# project_02.net
KiCad netlist of a schematic drawn in EAGLE
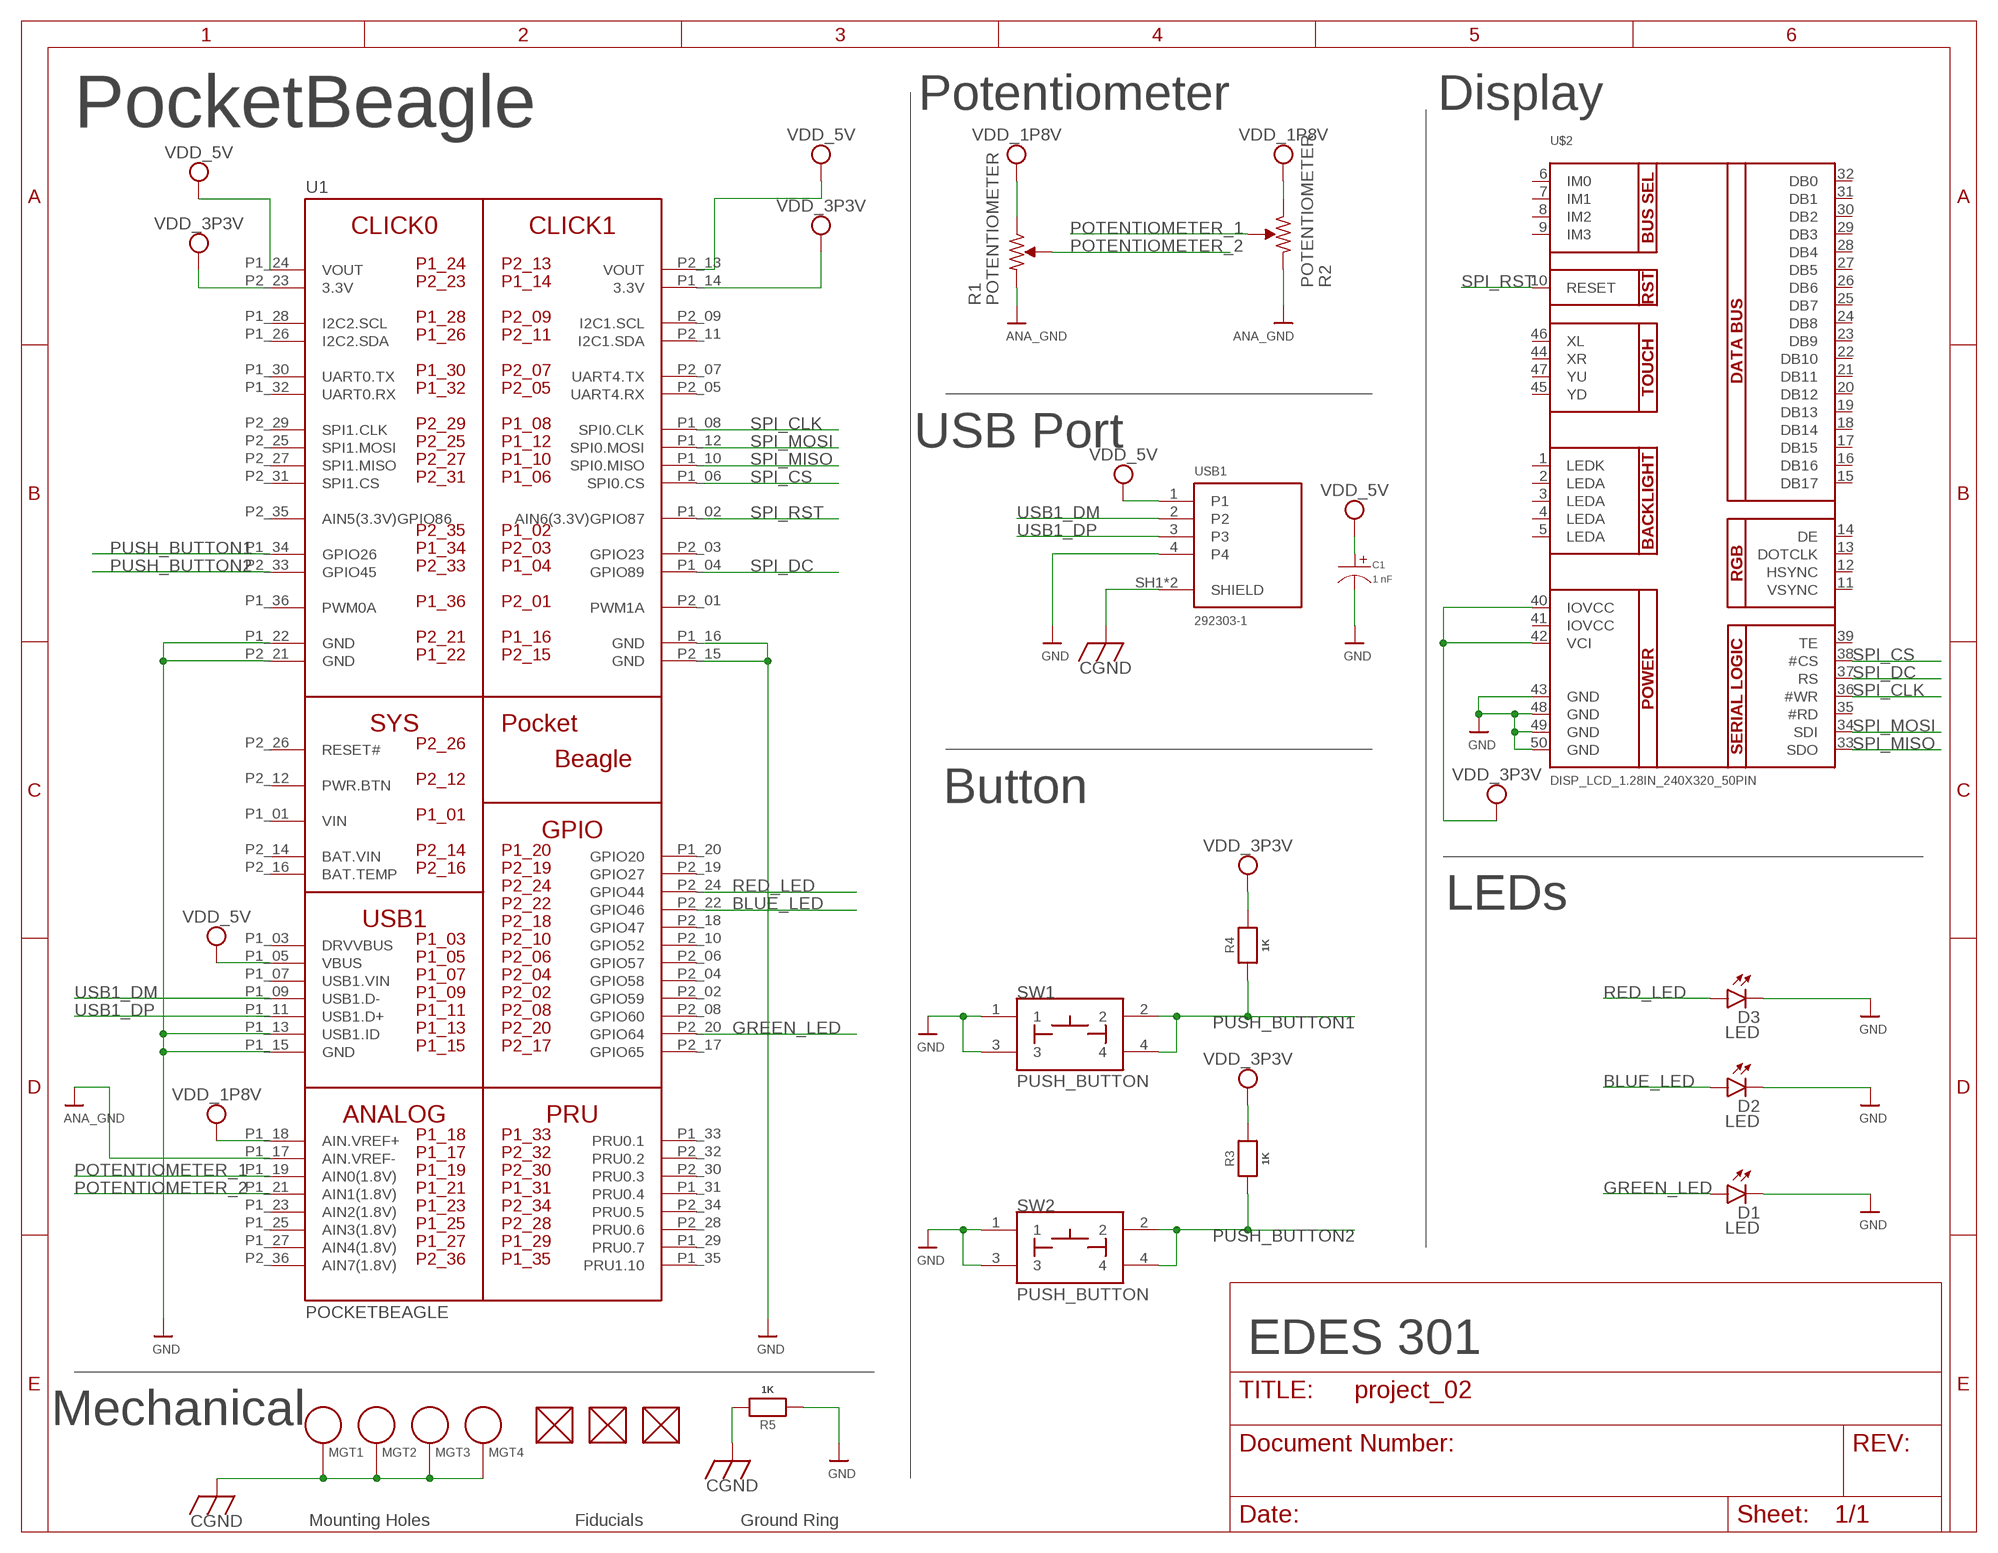
[diagram p0: schematic, sheet 1]

(export (version "E")
  (design (tool "Eeschema 10.0.6"))
  (components
    (comp (ref "C1")
      (value "1 nF")
      (footprint "eagle-import:CP4MM")
      (libsource (lib "eagle-import") (part "CAPACITOR_P_4MM"))
    )
    (comp (ref "D1")
      (value "LED")
      (footprint "eagle-import:LED3MM")
      (libsource (lib "eagle-import") (part "LED_13MM"))
    )
    (comp (ref "D2")
      (value "LED")
      (footprint "eagle-import:LED3MM")
      (libsource (lib "eagle-import") (part "LED_13MM"))
    )
    (comp (ref "D3")
      (value "LED")
      (footprint "eagle-import:LED3MM")
      (libsource (lib "eagle-import") (part "LED_13MM"))
    )
    (comp (ref "FUD2")
      (value "FIDUCIAL")
      (footprint "eagle-import:FIDUCIAL_40MIL")
      (libsource (lib "eagle-import") (part "FIDUCIAL"))
    )
    (comp (ref "FUD3")
      (value "FIDUCIAL")
      (footprint "eagle-import:FIDUCIAL_40MIL")
      (libsource (lib "eagle-import") (part "FIDUCIAL"))
    )
    (comp (ref "FUD4")
      (value "FIDUCIAL")
      (footprint "eagle-import:FIDUCIAL_40MIL")
      (libsource (lib "eagle-import") (part "FIDUCIAL"))
    )
    (comp (ref "MGT1")
      (value "MOUNTING_HOLE")
      (footprint "eagle-import:MOUNTING_HOLE")
      (libsource (lib "eagle-import") (part "MOUNTING_HOLE"))
    )
    (comp (ref "MGT2")
      (value "MOUNTING_HOLE")
      (footprint "eagle-import:MOUNTING_HOLE")
      (libsource (lib "eagle-import") (part "MOUNTING_HOLE"))
    )
    (comp (ref "MGT3")
      (value "MOUNTING_HOLE")
      (footprint "eagle-import:MOUNTING_HOLE")
      (libsource (lib "eagle-import") (part "MOUNTING_HOLE"))
    )
    (comp (ref "MGT4")
      (value "MOUNTING_HOLE")
      (footprint "eagle-import:MOUNTING_HOLE")
      (libsource (lib "eagle-import") (part "MOUNTING_HOLE"))
    )
    (comp (ref "R1")
      (value "POTENTIOMETER")
      (footprint "eagle-import:POT-PO90S")
      (libsource (lib "eagle-import") (part "POTENTIOMETER"))
    )
    (comp (ref "R2")
      (value "POTENTIOMETER")
      (footprint "eagle-import:POT-PO90S")
      (libsource (lib "eagle-import") (part "POTENTIOMETER"))
    )
    (comp (ref "R3")
      (value "1K")
      (footprint "eagle-import:0603-MINI")
      (libsource (lib "eagle-import") (part "RESISTOR0603MINI"))
    )
    (comp (ref "R4")
      (value "1K")
      (footprint "eagle-import:0603-MINI")
      (libsource (lib "eagle-import") (part "RESISTOR0603MINI"))
    )
    (comp (ref "R5")
      (value "1K")
      (footprint "eagle-import:0603-MINI")
      (libsource (lib "eagle-import") (part "RESISTOR0603MINI"))
    )
    (comp (ref "SW1")
      (value "PUSH_BUTTON")
      (footprint "eagle-import:BUTTON_12.5MM")
      (libsource (lib "eagle-import") (part "PUSH_BUTTON"))
    )
    (comp (ref "SW2")
      (value "PUSH_BUTTON")
      (footprint "eagle-import:BUTTON_12.5MM")
      (libsource (lib "eagle-import") (part "PUSH_BUTTON"))
    )
    (comp (ref "U$2")
      (value "DISP_LCD_1.28IN_240X320_50PIN")
      (footprint "eagle-import:TFT_2.83IN_240X320_50PIN")
      (libsource (lib "eagle-import") (part "DISP_LCD_1.28IN_240X320_50PIN"))
    )
    (comp (ref "U1")
      (value "POCKETBEAGLE")
      (footprint "eagle-import:POCKETBEAGLE")
      (libsource (lib "eagle-import") (part "POCKETBEAGLE"))
    )
    (comp (ref "USB1")
      (value "292303-1")
      (footprint "eagle-import:TE_292303-1")
      (fields (field (name "MF") "TE Connectivity"))
      (libsource (lib "eagle-import") (part "292303-1"))
    )
  )
  (nets
    (net (code "1") (name "/BAT.VIN") (class "Default")
      (node (ref "U1") (pin "P2_14") (pinfunction "BAT.VIN_P2_14") (pintype "power_in"))
    )
    (net (code "2") (name "/BLUE_LED") (class "Default")
      (node (ref "D2") (pin "A") (pinfunction "A_A") (pintype "passive"))
      (node (ref "U1") (pin "P2_22") (pinfunction "GPIO46_P2_22") (pintype "bidirectional"))
    )
    (net (code "3") (name "/GREEN_LED") (class "Default")
      (node (ref "D1") (pin "A") (pinfunction "A_A") (pintype "passive"))
      (node (ref "U1") (pin "P2_20") (pinfunction "GPIO64_P2_20") (pintype "bidirectional"))
    )
    (net (code "4") (name "/POTENTIOMETER_1") (class "Default")
      (node (ref "R2") (pin "S") (pinfunction "S_S") (pintype "bidirectional"))
      (node (ref "U1") (pin "P1_19") (pinfunction "AIN0(1.8V)_P1_19") (pintype "input"))
    )
    (net (code "5") (name "/POTENTIOMETER_2") (class "Default")
      (node (ref "R1") (pin "S") (pinfunction "S_S") (pintype "bidirectional"))
      (node (ref "U1") (pin "P1_21") (pinfunction "AIN1(1.8V)_P1_21") (pintype "input"))
    )
    (net (code "6") (name "/PUSH_BUTTON1") (class "Default")
      (node (ref "R4") (pin "1") (pinfunction "1_1") (pintype "passive"))
      (node (ref "SW1") (pin "2") (pinfunction "2_2") (pintype "bidirectional"))
      (node (ref "SW1") (pin "4") (pinfunction "4_4") (pintype "bidirectional"))
      (node (ref "U1") (pin "P1_34") (pinfunction "GPIO26_P1_34") (pintype "bidirectional"))
    )
    (net (code "7") (name "/PUSH_BUTTON2") (class "Default")
      (node (ref "R3") (pin "1") (pinfunction "1_1") (pintype "passive"))
      (node (ref "SW2") (pin "2") (pinfunction "2_2") (pintype "bidirectional"))
      (node (ref "SW2") (pin "4") (pinfunction "4_4") (pintype "bidirectional"))
      (node (ref "U1") (pin "P2_33") (pinfunction "GPIO45_P2_33") (pintype "bidirectional"))
    )
    (net (code "8") (name "/RED_LED") (class "Default")
      (node (ref "D3") (pin "A") (pinfunction "A_A") (pintype "passive"))
      (node (ref "U1") (pin "P2_24") (pinfunction "GPIO44_P2_24") (pintype "bidirectional"))
    )
    (net (code "9") (name "/SPI_CLK") (class "Default")
      (node (ref "U$2") (pin "36") (pinfunction "#WR_36") (pintype "bidirectional"))
      (node (ref "U1") (pin "P1_08") (pinfunction "SPI0.CLK_P1_08") (pintype "bidirectional"))
    )
    (net (code "10") (name "/SPI_CS") (class "Default")
      (node (ref "U$2") (pin "38") (pinfunction "#CS_38") (pintype "bidirectional"))
      (node (ref "U1") (pin "P1_06") (pinfunction "SPI0.CS_P1_06") (pintype "bidirectional"))
    )
    (net (code "11") (name "/SPI_DC") (class "Default")
      (node (ref "U$2") (pin "37") (pinfunction "RS_37") (pintype "bidirectional"))
      (node (ref "U1") (pin "P1_04") (pinfunction "GPIO89_P1_04") (pintype "bidirectional"))
    )
    (net (code "12") (name "/SPI_MISO") (class "Default")
      (node (ref "U$2") (pin "33") (pinfunction "SDO_33") (pintype "bidirectional"))
      (node (ref "U1") (pin "P1_10") (pinfunction "SPI0.MISO_P1_10") (pintype "bidirectional"))
    )
    (net (code "13") (name "/SPI_MOSI") (class "Default")
      (node (ref "U$2") (pin "34") (pinfunction "SDI_34") (pintype "bidirectional"))
      (node (ref "U1") (pin "P1_12") (pinfunction "SPI0.MOSI_P1_12") (pintype "bidirectional"))
    )
    (net (code "14") (name "/SPI_RST") (class "Default")
      (node (ref "U$2") (pin "10") (pinfunction "RESET_10") (pintype "bidirectional"))
      (node (ref "U1") (pin "P1_02") (pinfunction "AIN6(3.3V)GPIO87_P1_02") (pintype "bidirectional"))
    )
    (net (code "15") (name "/USB1_DM") (class "Default")
      (node (ref "U1") (pin "P1_09") (pinfunction "USB1.D-_P1_09") (pintype "bidirectional"))
      (node (ref "USB1") (pin "2") (pinfunction "P2_2") (pintype "passive"))
    )
    (net (code "16") (name "/USB1_DP") (class "Default")
      (node (ref "U1") (pin "P1_11") (pinfunction "USB1.D+_P1_11") (pintype "bidirectional"))
      (node (ref "USB1") (pin "3") (pinfunction "P3_3") (pintype "passive"))
    )
    (net (code "17") (name "/VIN") (class "Default")
      (node (ref "U1") (pin "P1_01") (pinfunction "VIN_P1_01") (pintype "power_in"))
    )
    (net (code "18") (name "ANA_GND") (class "Default")
      (node (ref "C1") (pin "P$2") (pinfunction "P$2_P$2") (pintype "passive"))
      (node (ref "D1") (pin "K") (pinfunction "C_K") (pintype "passive"))
      (node (ref "D2") (pin "K") (pinfunction "C_K") (pintype "passive"))
      (node (ref "D3") (pin "K") (pinfunction "C_K") (pintype "passive"))
      (node (ref "R1") (pin "CW") (pinfunction "CW_CW") (pintype "passive"))
      (node (ref "R2") (pin "CW") (pinfunction "CW_CW") (pintype "passive"))
      (node (ref "R5") (pin "1") (pinfunction "1_1") (pintype "passive"))
      (node (ref "SW1") (pin "1") (pinfunction "1_1") (pintype "bidirectional"))
      (node (ref "SW1") (pin "3") (pinfunction "3_3") (pintype "bidirectional"))
      (node (ref "SW2") (pin "1") (pinfunction "1_1") (pintype "bidirectional"))
      (node (ref "SW2") (pin "3") (pinfunction "3_3") (pintype "bidirectional"))
      (node (ref "U$2") (pin "43") (pinfunction "GND_43") (pintype "bidirectional"))
      (node (ref "U$2") (pin "48") (pinfunction "GND_48") (pintype "bidirectional"))
      (node (ref "U$2") (pin "49") (pinfunction "GND_49") (pintype "bidirectional"))
      (node (ref "U$2") (pin "50") (pinfunction "GND_50") (pintype "bidirectional"))
      (node (ref "U1") (pin "P1_13") (pinfunction "USB1.ID_P1_13") (pintype "bidirectional"))
      (node (ref "U1") (pin "P1_15") (pinfunction "GND_P1_15") (pintype "bidirectional"))
      (node (ref "U1") (pin "P1_16") (pinfunction "GND_P1_16") (pintype "power_in"))
      (node (ref "U1") (pin "P1_17") (pinfunction "AIN.VREF-_P1_17") (pintype "input"))
      (node (ref "U1") (pin "P1_22") (pinfunction "GND_P1_22") (pintype "power_in"))
      (node (ref "U1") (pin "P2_15") (pinfunction "GND_P2_15") (pintype "power_in"))
      (node (ref "U1") (pin "P2_21") (pinfunction "GND_P2_21") (pintype "power_in"))
      (node (ref "USB1") (pin "4") (pinfunction "P4_4") (pintype "passive"))
    )
    (net (code "19") (name "CGND") (class "Default")
      (node (ref "MGT1") (pin "P$1") (pinfunction "P$1_P$1") (pintype "bidirectional"))
      (node (ref "MGT2") (pin "P$1") (pinfunction "P$1_P$1") (pintype "bidirectional"))
      (node (ref "MGT3") (pin "P$1") (pinfunction "P$1_P$1") (pintype "bidirectional"))
      (node (ref "MGT4") (pin "P$1") (pinfunction "P$1_P$1") (pintype "bidirectional"))
      (node (ref "R5") (pin "2") (pinfunction "2_2") (pintype "passive"))
      (node (ref "USB1") (pin "SH1") (pinfunction "SHIELD_SH1") (pintype "passive"))
      (node (ref "USB1") (pin "SH2") (pinfunction "SHIELD_SH2") (pintype "passive"))
    )
    (net (code "20") (name "VDD_1P8V") (class "Default")
      (node (ref "R1") (pin "CCW") (pinfunction "CCW_CCW") (pintype "passive"))
      (node (ref "R2") (pin "CCW") (pinfunction "CCW_CCW") (pintype "passive"))
      (node (ref "U1") (pin "P1_18") (pinfunction "AIN.VREF+_P1_18") (pintype "input"))
    )
    (net (code "21") (name "VDD_3P3V") (class "Default")
      (node (ref "R3") (pin "2") (pinfunction "2_2") (pintype "passive"))
      (node (ref "R4") (pin "2") (pinfunction "2_2") (pintype "passive"))
      (node (ref "U$2") (pin "40") (pinfunction "IOVCC_40") (pintype "bidirectional"))
      (node (ref "U$2") (pin "42") (pinfunction "VCI_42") (pintype "bidirectional"))
      (node (ref "U1") (pin "P1_14") (pinfunction "3.3V_P1_14") (pintype "power_in"))
      (node (ref "U1") (pin "P2_23") (pinfunction "3.3V_P2_23") (pintype "power_in"))
    )
    (net (code "22") (name "VDD_5V") (class "Default")
      (node (ref "C1") (pin "P$1") (pinfunction "P$1_P$1") (pintype "passive"))
      (node (ref "U1") (pin "P1_05") (pinfunction "VBUS_P1_05") (pintype "bidirectional"))
      (node (ref "U1") (pin "P1_24") (pinfunction "VOUT_P1_24") (pintype "power_in"))
      (node (ref "U1") (pin "P2_13") (pinfunction "VOUT_P2_13") (pintype "power_in"))
      (node (ref "USB1") (pin "1") (pinfunction "P1_1") (pintype "passive"))
    )
    (net (code "23") (name "unconnected-(FUD2-PadP$1)") (class "Default")
      (node (ref "FUD2") (pin "P$1") (pinfunction "P$1_P$1") (pintype "no_connect"))
    )
    (net (code "24") (name "unconnected-(FUD3-PadP$1)") (class "Default")
      (node (ref "FUD3") (pin "P$1") (pinfunction "P$1_P$1") (pintype "no_connect"))
    )
    (net (code "25") (name "unconnected-(FUD4-PadP$1)") (class "Default")
      (node (ref "FUD4") (pin "P$1") (pinfunction "P$1_P$1") (pintype "no_connect"))
    )
    (net (code "26") (name "unconnected-(U$2-#RD-Pad35)") (class "Default")
      (node (ref "U$2") (pin "35") (pinfunction "#RD_35") (pintype "bidirectional"))
    )
    (net (code "27") (name "unconnected-(U$2-DB0-Pad32)") (class "Default")
      (node (ref "U$2") (pin "32") (pinfunction "DB0_32") (pintype "bidirectional"))
    )
    (net (code "28") (name "unconnected-(U$2-DB1-Pad31)") (class "Default")
      (node (ref "U$2") (pin "31") (pinfunction "DB1_31") (pintype "bidirectional"))
    )
    (net (code "29") (name "unconnected-(U$2-DB2-Pad30)") (class "Default")
      (node (ref "U$2") (pin "30") (pinfunction "DB2_30") (pintype "bidirectional"))
    )
    (net (code "30") (name "unconnected-(U$2-DB3-Pad29)") (class "Default")
      (node (ref "U$2") (pin "29") (pinfunction "DB3_29") (pintype "bidirectional"))
    )
    (net (code "31") (name "unconnected-(U$2-DB4-Pad28)") (class "Default")
      (node (ref "U$2") (pin "28") (pinfunction "DB4_28") (pintype "bidirectional"))
    )
    (net (code "32") (name "unconnected-(U$2-DB5-Pad27)") (class "Default")
      (node (ref "U$2") (pin "27") (pinfunction "DB5_27") (pintype "bidirectional"))
    )
    (net (code "33") (name "unconnected-(U$2-DB6-Pad26)") (class "Default")
      (node (ref "U$2") (pin "26") (pinfunction "DB6_26") (pintype "bidirectional"))
    )
    (net (code "34") (name "unconnected-(U$2-DB7-Pad25)") (class "Default")
      (node (ref "U$2") (pin "25") (pinfunction "DB7_25") (pintype "bidirectional"))
    )
    (net (code "35") (name "unconnected-(U$2-DB8-Pad24)") (class "Default")
      (node (ref "U$2") (pin "24") (pinfunction "DB8_24") (pintype "bidirectional"))
    )
    (net (code "36") (name "unconnected-(U$2-DB9-Pad23)") (class "Default")
      (node (ref "U$2") (pin "23") (pinfunction "DB9_23") (pintype "bidirectional"))
    )
    (net (code "37") (name "unconnected-(U$2-DB10-Pad22)") (class "Default")
      (node (ref "U$2") (pin "22") (pinfunction "DB10_22") (pintype "bidirectional"))
    )
    (net (code "38") (name "unconnected-(U$2-DB11-Pad21)") (class "Default")
      (node (ref "U$2") (pin "21") (pinfunction "DB11_21") (pintype "bidirectional"))
    )
    (net (code "39") (name "unconnected-(U$2-DB12-Pad20)") (class "Default")
      (node (ref "U$2") (pin "20") (pinfunction "DB12_20") (pintype "bidirectional"))
    )
    (net (code "40") (name "unconnected-(U$2-DB13-Pad19)") (class "Default")
      (node (ref "U$2") (pin "19") (pinfunction "DB13_19") (pintype "bidirectional"))
    )
    (net (code "41") (name "unconnected-(U$2-DB14-Pad18)") (class "Default")
      (node (ref "U$2") (pin "18") (pinfunction "DB14_18") (pintype "bidirectional"))
    )
    (net (code "42") (name "unconnected-(U$2-DB15-Pad17)") (class "Default")
      (node (ref "U$2") (pin "17") (pinfunction "DB15_17") (pintype "bidirectional"))
    )
    (net (code "43") (name "unconnected-(U$2-DB16-Pad16)") (class "Default")
      (node (ref "U$2") (pin "16") (pinfunction "DB16_16") (pintype "bidirectional"))
    )
    (net (code "44") (name "unconnected-(U$2-DB17-Pad15)") (class "Default")
      (node (ref "U$2") (pin "15") (pinfunction "DB17_15") (pintype "bidirectional"))
    )
    (net (code "45") (name "unconnected-(U$2-DE-Pad14)") (class "Default")
      (node (ref "U$2") (pin "14") (pinfunction "DE_14") (pintype "bidirectional"))
    )
    (net (code "46") (name "unconnected-(U$2-DOTCLK-Pad13)") (class "Default")
      (node (ref "U$2") (pin "13") (pinfunction "DOTCLK_13") (pintype "bidirectional"))
    )
    (net (code "47") (name "unconnected-(U$2-HSYNC-Pad12)") (class "Default")
      (node (ref "U$2") (pin "12") (pinfunction "HSYNC_12") (pintype "bidirectional"))
    )
    (net (code "48") (name "unconnected-(U$2-IM0-Pad6)") (class "Default")
      (node (ref "U$2") (pin "6") (pinfunction "IM0_6") (pintype "bidirectional"))
    )
    (net (code "49") (name "unconnected-(U$2-IM1-Pad7)") (class "Default")
      (node (ref "U$2") (pin "7") (pinfunction "IM1_7") (pintype "bidirectional"))
    )
    (net (code "50") (name "unconnected-(U$2-IM2-Pad8)") (class "Default")
      (node (ref "U$2") (pin "8") (pinfunction "IM2_8") (pintype "bidirectional"))
    )
    (net (code "51") (name "unconnected-(U$2-IM3-Pad9)") (class "Default")
      (node (ref "U$2") (pin "9") (pinfunction "IM3_9") (pintype "bidirectional"))
    )
    (net (code "52") (name "unconnected-(U$2-IOVCC-Pad41)") (class "Default")
      (node (ref "U$2") (pin "41") (pinfunction "IOVCC_41") (pintype "bidirectional"))
    )
    (net (code "53") (name "unconnected-(U$2-LEDA-Pad2)") (class "Default")
      (node (ref "U$2") (pin "2") (pinfunction "LEDA_2") (pintype "bidirectional"))
    )
    (net (code "54") (name "unconnected-(U$2-LEDA-Pad3)") (class "Default")
      (node (ref "U$2") (pin "3") (pinfunction "LEDA_3") (pintype "bidirectional"))
    )
    (net (code "55") (name "unconnected-(U$2-LEDA-Pad4)") (class "Default")
      (node (ref "U$2") (pin "4") (pinfunction "LEDA_4") (pintype "bidirectional"))
    )
    (net (code "56") (name "unconnected-(U$2-LEDA-Pad5)") (class "Default")
      (node (ref "U$2") (pin "5") (pinfunction "LEDA_5") (pintype "bidirectional"))
    )
    (net (code "57") (name "unconnected-(U$2-LEDK-Pad1)") (class "Default")
      (node (ref "U$2") (pin "1") (pinfunction "LEDK_1") (pintype "bidirectional"))
    )
    (net (code "58") (name "unconnected-(U$2-TE-Pad39)") (class "Default")
      (node (ref "U$2") (pin "39") (pinfunction "TE_39") (pintype "bidirectional"))
    )
    (net (code "59") (name "unconnected-(U$2-VSYNC-Pad11)") (class "Default")
      (node (ref "U$2") (pin "11") (pinfunction "VSYNC_11") (pintype "bidirectional"))
    )
    (net (code "60") (name "unconnected-(U$2-XL-Pad46)") (class "Default")
      (node (ref "U$2") (pin "46") (pinfunction "XL_46") (pintype "bidirectional"))
    )
    (net (code "61") (name "unconnected-(U$2-XR-Pad44)") (class "Default")
      (node (ref "U$2") (pin "44") (pinfunction "XR_44") (pintype "bidirectional"))
    )
    (net (code "62") (name "unconnected-(U$2-YD-Pad45)") (class "Default")
      (node (ref "U$2") (pin "45") (pinfunction "YD_45") (pintype "bidirectional"))
    )
    (net (code "63") (name "unconnected-(U$2-YU-Pad47)") (class "Default")
      (node (ref "U$2") (pin "47") (pinfunction "YU_47") (pintype "bidirectional"))
    )
    (net (code "64") (name "unconnected-(U1-AIN2(1.8V)-PadP1_23)") (class "Default")
      (node (ref "U1") (pin "P1_23") (pinfunction "AIN2(1.8V)_P1_23") (pintype "input"))
    )
    (net (code "65") (name "unconnected-(U1-AIN3(1.8V)-PadP1_25)") (class "Default")
      (node (ref "U1") (pin "P1_25") (pinfunction "AIN3(1.8V)_P1_25") (pintype "input"))
    )
    (net (code "66") (name "unconnected-(U1-AIN4(1.8V)-PadP1_27)") (class "Default")
      (node (ref "U1") (pin "P1_27") (pinfunction "AIN4(1.8V)_P1_27") (pintype "input"))
    )
    (net (code "67") (name "unconnected-(U1-AIN5(3.3V)GPIO86-PadP2_35)") (class "Default")
      (node (ref "U1") (pin "P2_35") (pinfunction "AIN5(3.3V)GPIO86_P2_35") (pintype "bidirectional"))
    )
    (net (code "68") (name "unconnected-(U1-AIN7(1.8V)-PadP2_36)") (class "Default")
      (node (ref "U1") (pin "P2_36") (pinfunction "AIN7(1.8V)_P2_36") (pintype "input"))
    )
    (net (code "69") (name "unconnected-(U1-BAT.TEMP-PadP2_16)") (class "Default")
      (node (ref "U1") (pin "P2_16") (pinfunction "BAT.TEMP_P2_16") (pintype "input"))
    )
    (net (code "70") (name "unconnected-(U1-DRVVBUS-PadP1_03)") (class "Default")
      (node (ref "U1") (pin "P1_03") (pinfunction "DRVVBUS_P1_03") (pintype "bidirectional"))
    )
    (net (code "71") (name "unconnected-(U1-GPIO20-PadP1_20)") (class "Default")
      (node (ref "U1") (pin "P1_20") (pinfunction "GPIO20_P1_20") (pintype "bidirectional"))
    )
    (net (code "72") (name "unconnected-(U1-GPIO23-PadP2_03)") (class "Default")
      (node (ref "U1") (pin "P2_03") (pinfunction "GPIO23_P2_03") (pintype "bidirectional"))
    )
    (net (code "73") (name "unconnected-(U1-GPIO27-PadP2_19)") (class "Default")
      (node (ref "U1") (pin "P2_19") (pinfunction "GPIO27_P2_19") (pintype "bidirectional"))
    )
    (net (code "74") (name "unconnected-(U1-GPIO47-PadP2_18)") (class "Default")
      (node (ref "U1") (pin "P2_18") (pinfunction "GPIO47_P2_18") (pintype "bidirectional"))
    )
    (net (code "75") (name "unconnected-(U1-GPIO52-PadP2_10)") (class "Default")
      (node (ref "U1") (pin "P2_10") (pinfunction "GPIO52_P2_10") (pintype "bidirectional"))
    )
    (net (code "76") (name "unconnected-(U1-GPIO57-PadP2_06)") (class "Default")
      (node (ref "U1") (pin "P2_06") (pinfunction "GPIO57_P2_06") (pintype "bidirectional"))
    )
    (net (code "77") (name "unconnected-(U1-GPIO58-PadP2_04)") (class "Default")
      (node (ref "U1") (pin "P2_04") (pinfunction "GPIO58_P2_04") (pintype "bidirectional"))
    )
    (net (code "78") (name "unconnected-(U1-GPIO59-PadP2_02)") (class "Default")
      (node (ref "U1") (pin "P2_02") (pinfunction "GPIO59_P2_02") (pintype "bidirectional"))
    )
    (net (code "79") (name "unconnected-(U1-GPIO60-PadP2_08)") (class "Default")
      (node (ref "U1") (pin "P2_08") (pinfunction "GPIO60_P2_08") (pintype "bidirectional"))
    )
    (net (code "80") (name "unconnected-(U1-GPIO65-PadP2_17)") (class "Default")
      (node (ref "U1") (pin "P2_17") (pinfunction "GPIO65_P2_17") (pintype "bidirectional"))
    )
    (net (code "81") (name "unconnected-(U1-I2C1.SCL-PadP2_09)") (class "Default")
      (node (ref "U1") (pin "P2_09") (pinfunction "I2C1.SCL_P2_09") (pintype "bidirectional"))
    )
    (net (code "82") (name "unconnected-(U1-I2C1.SDA-PadP2_11)") (class "Default")
      (node (ref "U1") (pin "P2_11") (pinfunction "I2C1.SDA_P2_11") (pintype "bidirectional"))
    )
    (net (code "83") (name "unconnected-(U1-I2C2.SCL-PadP1_28)") (class "Default")
      (node (ref "U1") (pin "P1_28") (pinfunction "I2C2.SCL_P1_28") (pintype "bidirectional"))
    )
    (net (code "84") (name "unconnected-(U1-I2C2.SDA-PadP1_26)") (class "Default")
      (node (ref "U1") (pin "P1_26") (pinfunction "I2C2.SDA_P1_26") (pintype "bidirectional"))
    )
    (net (code "85") (name "unconnected-(U1-PRU0.1-PadP1_33)") (class "Default")
      (node (ref "U1") (pin "P1_33") (pinfunction "PRU0.1_P1_33") (pintype "bidirectional"))
    )
    (net (code "86") (name "unconnected-(U1-PRU0.2-PadP2_32)") (class "Default")
      (node (ref "U1") (pin "P2_32") (pinfunction "PRU0.2_P2_32") (pintype "bidirectional"))
    )
    (net (code "87") (name "unconnected-(U1-PRU0.3-PadP2_30)") (class "Default")
      (node (ref "U1") (pin "P2_30") (pinfunction "PRU0.3_P2_30") (pintype "bidirectional"))
    )
    (net (code "88") (name "unconnected-(U1-PRU0.4-PadP1_31)") (class "Default")
      (node (ref "U1") (pin "P1_31") (pinfunction "PRU0.4_P1_31") (pintype "bidirectional"))
    )
    (net (code "89") (name "unconnected-(U1-PRU0.5-PadP2_34)") (class "Default")
      (node (ref "U1") (pin "P2_34") (pinfunction "PRU0.5_P2_34") (pintype "bidirectional"))
    )
    (net (code "90") (name "unconnected-(U1-PRU0.6-PadP2_28)") (class "Default")
      (node (ref "U1") (pin "P2_28") (pinfunction "PRU0.6_P2_28") (pintype "bidirectional"))
    )
    (net (code "91") (name "unconnected-(U1-PRU0.7-PadP1_29)") (class "Default")
      (node (ref "U1") (pin "P1_29") (pinfunction "PRU0.7_P1_29") (pintype "bidirectional"))
    )
    (net (code "92") (name "unconnected-(U1-PRU1.10-PadP1_35)") (class "Default")
      (node (ref "U1") (pin "P1_35") (pinfunction "PRU1.10_P1_35") (pintype "bidirectional"))
    )
    (net (code "93") (name "unconnected-(U1-PWM0A-PadP1_36)") (class "Default")
      (node (ref "U1") (pin "P1_36") (pinfunction "PWM0A_P1_36") (pintype "bidirectional"))
    )
    (net (code "94") (name "unconnected-(U1-PWM1A-PadP2_01)") (class "Default")
      (node (ref "U1") (pin "P2_01") (pinfunction "PWM1A_P2_01") (pintype "bidirectional"))
    )
    (net (code "95") (name "unconnected-(U1-PWR.BTN-PadP2_12)") (class "Default")
      (node (ref "U1") (pin "P2_12") (pinfunction "PWR.BTN_P2_12") (pintype "input"))
    )
    (net (code "96") (name "unconnected-(U1-RESET#-PadP2_26)") (class "Default")
      (node (ref "U1") (pin "P2_26") (pinfunction "RESET#_P2_26") (pintype "input"))
    )
    (net (code "97") (name "unconnected-(U1-SPI1.CLK-PadP2_29)") (class "Default")
      (node (ref "U1") (pin "P2_29") (pinfunction "SPI1.CLK_P2_29") (pintype "bidirectional"))
    )
    (net (code "98") (name "unconnected-(U1-SPI1.CS-PadP2_31)") (class "Default")
      (node (ref "U1") (pin "P2_31") (pinfunction "SPI1.CS_P2_31") (pintype "bidirectional"))
    )
    (net (code "99") (name "unconnected-(U1-SPI1.MISO-PadP2_27)") (class "Default")
      (node (ref "U1") (pin "P2_27") (pinfunction "SPI1.MISO_P2_27") (pintype "bidirectional"))
    )
    (net (code "100") (name "unconnected-(U1-SPI1.MOSI-PadP2_25)") (class "Default")
      (node (ref "U1") (pin "P2_25") (pinfunction "SPI1.MOSI_P2_25") (pintype "bidirectional"))
    )
    (net (code "101") (name "unconnected-(U1-UART0.RX-PadP1_32)") (class "Default")
      (node (ref "U1") (pin "P1_32") (pinfunction "UART0.RX_P1_32") (pintype "bidirectional"))
    )
    (net (code "102") (name "unconnected-(U1-UART0.TX-PadP1_30)") (class "Default")
      (node (ref "U1") (pin "P1_30") (pinfunction "UART0.TX_P1_30") (pintype "bidirectional"))
    )
    (net (code "103") (name "unconnected-(U1-UART4.RX-PadP2_05)") (class "Default")
      (node (ref "U1") (pin "P2_05") (pinfunction "UART4.RX_P2_05") (pintype "bidirectional"))
    )
    (net (code "104") (name "unconnected-(U1-UART4.TX-PadP2_07)") (class "Default")
      (node (ref "U1") (pin "P2_07") (pinfunction "UART4.TX_P2_07") (pintype "bidirectional"))
    )
    (net (code "105") (name "unconnected-(U1-USB1.VIN-PadP1_07)") (class "Default")
      (node (ref "U1") (pin "P1_07") (pinfunction "USB1.VIN_P1_07") (pintype "bidirectional"))
    )
  )
)
